# simpleglitcher.net
KiCad netlist of a schematic drawn in EAGLE
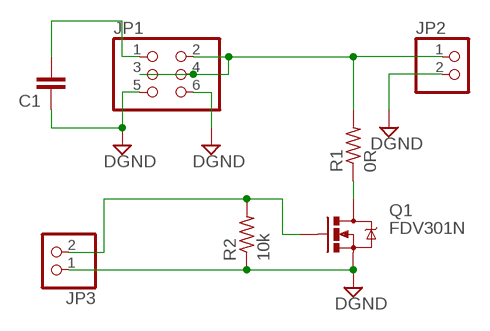
[diagram p0: schematic, sheet 1]

(export (version "E")
  (design (tool "Eeschema 10.0.6"))
  (components
    (comp (ref "C1")
      (value "C-EUC0603")
      (footprint "eagle-import:C0603")
      (libsource (lib "eagle-import") (part "C-EUC0603"))
    )
    (comp (ref "JP1")
      (value "PINHD-2X3")
      (footprint "eagle-import:2X03")
      (libsource (lib "eagle-import") (part "PINHD-2X3"))
    )
    (comp (ref "JP2")
      (value "PINHD-1X2")
      (footprint "eagle-import:1X02")
      (libsource (lib "eagle-import") (part "PINHD-1X2"))
    )
    (comp (ref "JP3")
      (value "PINHD-1X2")
      (footprint "eagle-import:1X02")
      (libsource (lib "eagle-import") (part "PINHD-1X2"))
    )
    (comp (ref "Q1")
      (value "FDV301N")
      (footprint "eagle-import:SOT23-3")
      (libsource (lib "eagle-import") (part "MOSFET-NCHANNELSMD"))
    )
    (comp (ref "R1")
      (value "0R")
      (footprint "eagle-import:R0603")
      (libsource (lib "eagle-import") (part "R-US_R0603"))
    )
    (comp (ref "R2")
      (value "10k")
      (footprint "eagle-import:R0603")
      (libsource (lib "eagle-import") (part "R-US_R0603"))
    )
  )
  (nets
    (net (code "1") (name "DGND") (class "Default")
      (node (ref "C1") (pin "1") (pinfunction "1_1") (pintype "passive"))
      (node (ref "JP1") (pin "5") (pinfunction "5_5") (pintype "passive"))
      (node (ref "JP1") (pin "6") (pinfunction "6_6") (pintype "passive"))
      (node (ref "JP2") (pin "2") (pinfunction "2_2") (pintype "passive"))
      (node (ref "JP3") (pin "1") (pinfunction "1_1") (pintype "passive"))
      (node (ref "Q1") (pin "2") (pinfunction "S_2") (pintype "passive"))
      (node (ref "R2") (pin "1") (pinfunction "1_1") (pintype "passive"))
    )
    (net (code "2") (name "Net-(C1-Pad2)") (class "Default")
      (node (ref "C1") (pin "2") (pinfunction "2_2") (pintype "passive"))
      (node (ref "JP1") (pin "1") (pinfunction "1_1") (pintype "passive"))
    )
    (net (code "3") (name "Net-(JP1-Pad2)") (class "Default")
      (node (ref "JP1") (pin "2") (pinfunction "2_2") (pintype "passive"))
      (node (ref "JP1") (pin "3") (pinfunction "3_3") (pintype "passive"))
      (node (ref "JP1") (pin "4") (pinfunction "4_4") (pintype "passive"))
      (node (ref "JP2") (pin "1") (pinfunction "1_1") (pintype "passive"))
      (node (ref "R1") (pin "2") (pinfunction "2_2") (pintype "passive"))
    )
    (net (code "4") (name "Net-(Q1-D)") (class "Default")
      (node (ref "Q1") (pin "3") (pinfunction "D_3") (pintype "passive"))
      (node (ref "R1") (pin "1") (pinfunction "1_1") (pintype "passive"))
    )
    (net (code "5") (name "Net-(Q1-G)") (class "Default")
      (node (ref "JP3") (pin "2") (pinfunction "2_2") (pintype "passive"))
      (node (ref "Q1") (pin "1") (pinfunction "G_1") (pintype "passive"))
      (node (ref "R2") (pin "2") (pinfunction "2_2") (pintype "passive"))
    )
  )
)
